# Ch5and6.net
KiCad netlist of a schematic drawn in Altium Designer
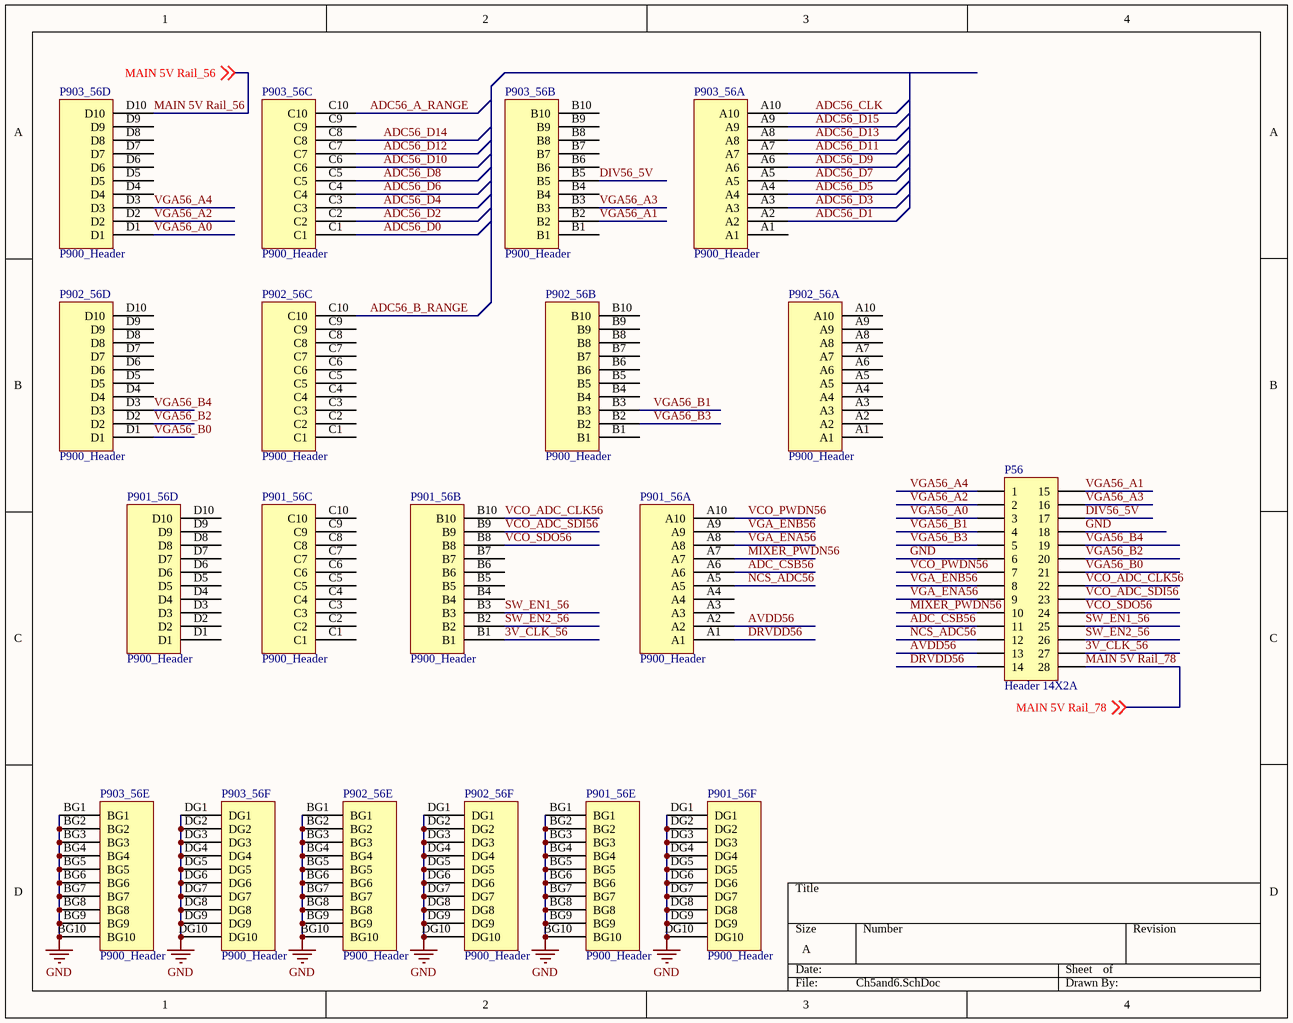
[diagram p0: Ch5and6.SchDoc]

(export (version "E")
  (design (tool "Eeschema 10.0.6"))
  (components
    (comp (ref "P56")
      (value "Header 14X2A")
      (footprint "HDR2X14_CEN")
      (description "Header, 14-Pin, Dual row")
      (fields (field (name "PUBLISHER") "Altium Limited"))
      (libsource (lib "Miscellaneous Connectors") (part "Header 14X2A"))
    )
    (comp (ref "P901_56")
      (value "P900_Header")
      (footprint "P900_header")
      (libsource (lib "") (part "P900_Header_1"))
    )
    (comp (ref "P902_56")
      (value "P900_Header")
      (footprint "P900_header")
      (libsource (lib "") (part "P900_Header_1"))
    )
    (comp (ref "P903_56")
      (value "P900_Header")
      (footprint "P900_header")
      (libsource (lib "MQP_lib") (part "P900_Header"))
    )
  )
  (nets
    (net (code "1") (name "/3V_CLK_56") (class "Default")
      (node (ref "P56") (pin "27") (pinfunction "27_27") (pintype "passive"))
      (node (ref "P901_56") (pin "B1") (pinfunction "B1_B1") (pintype "passive"))
    )
    (net (code "2") (name "/ADC56_A_RANGE") (class "Default")
      (node (ref "P903_56") (pin "C10") (pinfunction "C10_C10") (pintype "passive"))
    )
    (net (code "3") (name "/ADC56_B_RANGE") (class "Default")
      (node (ref "P902_56") (pin "C10") (pinfunction "C10_C10") (pintype "passive"))
    )
    (net (code "4") (name "/ADC56_CLK") (class "Default")
      (node (ref "P903_56") (pin "A10") (pinfunction "A10_A10") (pintype "passive"))
    )
    (net (code "5") (name "/ADC56_D0") (class "Default")
      (node (ref "P903_56") (pin "C1") (pinfunction "C1_C1") (pintype "passive"))
    )
    (net (code "6") (name "/ADC56_D1") (class "Default")
      (node (ref "P903_56") (pin "A2") (pinfunction "A2_A2") (pintype "passive"))
    )
    (net (code "7") (name "/ADC56_D2") (class "Default")
      (node (ref "P903_56") (pin "C2") (pinfunction "C2_C2") (pintype "passive"))
    )
    (net (code "8") (name "/ADC56_D3") (class "Default")
      (node (ref "P903_56") (pin "A3") (pinfunction "A3_A3") (pintype "passive"))
    )
    (net (code "9") (name "/ADC56_D4") (class "Default")
      (node (ref "P903_56") (pin "C3") (pinfunction "C3_C3") (pintype "passive"))
    )
    (net (code "10") (name "/ADC56_D5") (class "Default")
      (node (ref "P903_56") (pin "A4") (pinfunction "A4_A4") (pintype "passive"))
    )
    (net (code "11") (name "/ADC56_D6") (class "Default")
      (node (ref "P903_56") (pin "C4") (pinfunction "C4_C4") (pintype "passive"))
    )
    (net (code "12") (name "/ADC56_D7") (class "Default")
      (node (ref "P903_56") (pin "A5") (pinfunction "A5_A5") (pintype "passive"))
    )
    (net (code "13") (name "/ADC56_D8") (class "Default")
      (node (ref "P903_56") (pin "C5") (pinfunction "C5_C5") (pintype "passive"))
    )
    (net (code "14") (name "/ADC56_D9") (class "Default")
      (node (ref "P903_56") (pin "A6") (pinfunction "A6_A6") (pintype "passive"))
    )
    (net (code "15") (name "/ADC56_D10") (class "Default")
      (node (ref "P903_56") (pin "C6") (pinfunction "C6_C6") (pintype "passive"))
    )
    (net (code "16") (name "/ADC56_D11") (class "Default")
      (node (ref "P903_56") (pin "A7") (pinfunction "A7_A7") (pintype "passive"))
    )
    (net (code "17") (name "/ADC56_D12") (class "Default")
      (node (ref "P903_56") (pin "C7") (pinfunction "C7_C7") (pintype "passive"))
    )
    (net (code "18") (name "/ADC56_D13") (class "Default")
      (node (ref "P903_56") (pin "A8") (pinfunction "A8_A8") (pintype "passive"))
    )
    (net (code "19") (name "/ADC56_D14") (class "Default")
      (node (ref "P903_56") (pin "C8") (pinfunction "C8_C8") (pintype "passive"))
    )
    (net (code "20") (name "/ADC56_D15") (class "Default")
      (node (ref "P903_56") (pin "A9") (pinfunction "A9_A9") (pintype "passive"))
    )
    (net (code "21") (name "/ADC_CSB56") (class "Default")
      (node (ref "P56") (pin "11") (pinfunction "11_11") (pintype "passive"))
      (node (ref "P901_56") (pin "A6") (pinfunction "A6_A6") (pintype "passive"))
    )
    (net (code "22") (name "/AVDD56") (class "Default")
      (node (ref "P56") (pin "13") (pinfunction "13_13") (pintype "passive"))
      (node (ref "P901_56") (pin "A2") (pinfunction "A2_A2") (pintype "passive"))
    )
    (net (code "23") (name "/DIV56_5V") (class "Default")
      (node (ref "P56") (pin "17") (pinfunction "17_17") (pintype "passive"))
      (node (ref "P903_56") (pin "B5") (pinfunction "B5_B5") (pintype "passive"))
    )
    (net (code "24") (name "/DRVDD56") (class "Default")
      (node (ref "P56") (pin "14") (pinfunction "14_14") (pintype "passive"))
      (node (ref "P901_56") (pin "A1") (pinfunction "A1_A1") (pintype "passive"))
    )
    (net (code "25") (name "/MIXER_PWDN56") (class "Default")
      (node (ref "P56") (pin "10") (pinfunction "10_10") (pintype "passive"))
      (node (ref "P901_56") (pin "A7") (pinfunction "A7_A7") (pintype "passive"))
    )
    (net (code "26") (name "/NCS_ADC56") (class "Default")
      (node (ref "P56") (pin "12") (pinfunction "12_12") (pintype "passive"))
      (node (ref "P901_56") (pin "A5") (pinfunction "A5_A5") (pintype "passive"))
    )
    (net (code "27") (name "/SW_EN1_56") (class "Default")
      (node (ref "P56") (pin "25") (pinfunction "25_25") (pintype "passive"))
      (node (ref "P901_56") (pin "B3") (pinfunction "B3_B3") (pintype "passive"))
    )
    (net (code "28") (name "/SW_EN2_56") (class "Default")
      (node (ref "P56") (pin "26") (pinfunction "26_26") (pintype "passive"))
      (node (ref "P901_56") (pin "B2") (pinfunction "B2_B2") (pintype "passive"))
    )
    (net (code "29") (name "/VCO_ADC_CLK56") (class "Default")
      (node (ref "P56") (pin "22") (pinfunction "22_22") (pintype "passive"))
      (node (ref "P901_56") (pin "B10") (pinfunction "B10_B10") (pintype "passive"))
    )
    (net (code "30") (name "/VCO_ADC_SDI56") (class "Default")
      (node (ref "P56") (pin "23") (pinfunction "23_23") (pintype "passive"))
      (node (ref "P901_56") (pin "B9") (pinfunction "B9_B9") (pintype "passive"))
    )
    (net (code "31") (name "/VCO_PWDN56") (class "Default")
      (node (ref "P56") (pin "7") (pinfunction "7_7") (pintype "passive"))
      (node (ref "P901_56") (pin "A10") (pinfunction "A10_A10") (pintype "passive"))
    )
    (net (code "32") (name "/VCO_SDO56") (class "Default")
      (node (ref "P56") (pin "24") (pinfunction "24_24") (pintype "passive"))
      (node (ref "P901_56") (pin "B8") (pinfunction "B8_B8") (pintype "passive"))
    )
    (net (code "33") (name "/VGA56_A0") (class "Default")
      (node (ref "P56") (pin "3") (pinfunction "3_3") (pintype "passive"))
      (node (ref "P903_56") (pin "D1") (pinfunction "D1_D1") (pintype "passive"))
    )
    (net (code "34") (name "/VGA56_A1") (class "Default")
      (node (ref "P56") (pin "15") (pinfunction "15_15") (pintype "passive"))
      (node (ref "P903_56") (pin "B2") (pinfunction "B2_B2") (pintype "passive"))
    )
    (net (code "35") (name "/VGA56_A2") (class "Default")
      (node (ref "P56") (pin "2") (pinfunction "2_2") (pintype "passive"))
      (node (ref "P903_56") (pin "D2") (pinfunction "D2_D2") (pintype "passive"))
    )
    (net (code "36") (name "/VGA56_A3") (class "Default")
      (node (ref "P56") (pin "16") (pinfunction "16_16") (pintype "passive"))
      (node (ref "P903_56") (pin "B3") (pinfunction "B3_B3") (pintype "passive"))
    )
    (net (code "37") (name "/VGA56_A4") (class "Default")
      (node (ref "P56") (pin "1") (pinfunction "1_1") (pintype "passive"))
      (node (ref "P903_56") (pin "D3") (pinfunction "D3_D3") (pintype "passive"))
    )
    (net (code "38") (name "/VGA56_B0") (class "Default")
      (node (ref "P56") (pin "21") (pinfunction "21_21") (pintype "passive"))
      (node (ref "P902_56") (pin "D1") (pinfunction "D1_D1") (pintype "passive"))
    )
    (net (code "39") (name "/VGA56_B1") (class "Default")
      (node (ref "P56") (pin "4") (pinfunction "4_4") (pintype "passive"))
      (node (ref "P902_56") (pin "B3") (pinfunction "B3_B3") (pintype "passive"))
    )
    (net (code "40") (name "/VGA56_B2") (class "Default")
      (node (ref "P56") (pin "20") (pinfunction "20_20") (pintype "passive"))
      (node (ref "P902_56") (pin "D2") (pinfunction "D2_D2") (pintype "passive"))
    )
    (net (code "41") (name "/VGA56_B3") (class "Default")
      (node (ref "P56") (pin "5") (pinfunction "5_5") (pintype "passive"))
      (node (ref "P902_56") (pin "B2") (pinfunction "B2_B2") (pintype "passive"))
    )
    (net (code "42") (name "/VGA56_B4") (class "Default")
      (node (ref "P56") (pin "19") (pinfunction "19_19") (pintype "passive"))
      (node (ref "P902_56") (pin "D3") (pinfunction "D3_D3") (pintype "passive"))
    )
    (net (code "43") (name "/VGA_ENA56") (class "Default")
      (node (ref "P56") (pin "9") (pinfunction "9_9") (pintype "passive"))
      (node (ref "P901_56") (pin "A8") (pinfunction "A8_A8") (pintype "passive"))
    )
    (net (code "44") (name "/VGA_ENB56") (class "Default")
      (node (ref "P56") (pin "8") (pinfunction "8_8") (pintype "passive"))
      (node (ref "P901_56") (pin "A9") (pinfunction "A9_A9") (pintype "passive"))
    )
    (net (code "45") (name "GND") (class "Default")
      (node (ref "P56") (pin "18") (pinfunction "18_18") (pintype "passive"))
      (node (ref "P56") (pin "6") (pinfunction "6_6") (pintype "passive"))
      (node (ref "P901_56") (pin "BG1") (pinfunction "BG1_BG1") (pintype "passive"))
      (node (ref "P901_56") (pin "BG10") (pinfunction "BG10_BG10") (pintype "passive"))
      (node (ref "P901_56") (pin "BG2") (pinfunction "BG2_BG2") (pintype "passive"))
      (node (ref "P901_56") (pin "BG3") (pinfunction "BG3_BG3") (pintype "passive"))
      (node (ref "P901_56") (pin "BG4") (pinfunction "BG4_BG4") (pintype "passive"))
      (node (ref "P901_56") (pin "BG5") (pinfunction "BG5_BG5") (pintype "passive"))
      (node (ref "P901_56") (pin "BG6") (pinfunction "BG6_BG6") (pintype "passive"))
      (node (ref "P901_56") (pin "BG7") (pinfunction "BG7_BG7") (pintype "passive"))
      (node (ref "P901_56") (pin "BG8") (pinfunction "BG8_BG8") (pintype "passive"))
      (node (ref "P901_56") (pin "BG9") (pinfunction "BG9_BG9") (pintype "passive"))
      (node (ref "P901_56") (pin "DG1") (pinfunction "DG1_DG1") (pintype "passive"))
      (node (ref "P901_56") (pin "DG10") (pinfunction "DG10_DG10") (pintype "passive"))
      (node (ref "P901_56") (pin "DG2") (pinfunction "DG2_DG2") (pintype "passive"))
      (node (ref "P901_56") (pin "DG3") (pinfunction "DG3_DG3") (pintype "passive"))
      (node (ref "P901_56") (pin "DG4") (pinfunction "DG4_DG4") (pintype "passive"))
      (node (ref "P901_56") (pin "DG5") (pinfunction "DG5_DG5") (pintype "passive"))
      (node (ref "P901_56") (pin "DG6") (pinfunction "DG6_DG6") (pintype "passive"))
      (node (ref "P901_56") (pin "DG7") (pinfunction "DG7_DG7") (pintype "passive"))
      (node (ref "P901_56") (pin "DG8") (pinfunction "DG8_DG8") (pintype "passive"))
      (node (ref "P901_56") (pin "DG9") (pinfunction "DG9_DG9") (pintype "passive"))
      (node (ref "P902_56") (pin "BG1") (pinfunction "BG1_BG1") (pintype "passive"))
      (node (ref "P902_56") (pin "BG10") (pinfunction "BG10_BG10") (pintype "passive"))
      (node (ref "P902_56") (pin "BG2") (pinfunction "BG2_BG2") (pintype "passive"))
      (node (ref "P902_56") (pin "BG3") (pinfunction "BG3_BG3") (pintype "passive"))
      (node (ref "P902_56") (pin "BG4") (pinfunction "BG4_BG4") (pintype "passive"))
      (node (ref "P902_56") (pin "BG5") (pinfunction "BG5_BG5") (pintype "passive"))
      (node (ref "P902_56") (pin "BG6") (pinfunction "BG6_BG6") (pintype "passive"))
      (node (ref "P902_56") (pin "BG7") (pinfunction "BG7_BG7") (pintype "passive"))
      (node (ref "P902_56") (pin "BG8") (pinfunction "BG8_BG8") (pintype "passive"))
      (node (ref "P902_56") (pin "BG9") (pinfunction "BG9_BG9") (pintype "passive"))
      (node (ref "P902_56") (pin "DG1") (pinfunction "DG1_DG1") (pintype "passive"))
      (node (ref "P902_56") (pin "DG10") (pinfunction "DG10_DG10") (pintype "passive"))
      (node (ref "P902_56") (pin "DG2") (pinfunction "DG2_DG2") (pintype "passive"))
      (node (ref "P902_56") (pin "DG3") (pinfunction "DG3_DG3") (pintype "passive"))
      (node (ref "P902_56") (pin "DG4") (pinfunction "DG4_DG4") (pintype "passive"))
      (node (ref "P902_56") (pin "DG5") (pinfunction "DG5_DG5") (pintype "passive"))
      (node (ref "P902_56") (pin "DG6") (pinfunction "DG6_DG6") (pintype "passive"))
      (node (ref "P902_56") (pin "DG7") (pinfunction "DG7_DG7") (pintype "passive"))
      (node (ref "P902_56") (pin "DG8") (pinfunction "DG8_DG8") (pintype "passive"))
      (node (ref "P902_56") (pin "DG9") (pinfunction "DG9_DG9") (pintype "passive"))
      (node (ref "P903_56") (pin "BG1") (pinfunction "BG1_BG1") (pintype "passive"))
      (node (ref "P903_56") (pin "BG10") (pinfunction "BG10_BG10") (pintype "passive"))
      (node (ref "P903_56") (pin "BG2") (pinfunction "BG2_BG2") (pintype "passive"))
      (node (ref "P903_56") (pin "BG3") (pinfunction "BG3_BG3") (pintype "passive"))
      (node (ref "P903_56") (pin "BG4") (pinfunction "BG4_BG4") (pintype "passive"))
      (node (ref "P903_56") (pin "BG5") (pinfunction "BG5_BG5") (pintype "passive"))
      (node (ref "P903_56") (pin "BG6") (pinfunction "BG6_BG6") (pintype "passive"))
      (node (ref "P903_56") (pin "BG7") (pinfunction "BG7_BG7") (pintype "passive"))
      (node (ref "P903_56") (pin "BG8") (pinfunction "BG8_BG8") (pintype "passive"))
      (node (ref "P903_56") (pin "BG9") (pinfunction "BG9_BG9") (pintype "passive"))
      (node (ref "P903_56") (pin "DG1") (pinfunction "DG1_DG1") (pintype "passive"))
      (node (ref "P903_56") (pin "DG10") (pinfunction "DG10_DG10") (pintype "passive"))
      (node (ref "P903_56") (pin "DG2") (pinfunction "DG2_DG2") (pintype "passive"))
      (node (ref "P903_56") (pin "DG3") (pinfunction "DG3_DG3") (pintype "passive"))
      (node (ref "P903_56") (pin "DG4") (pinfunction "DG4_DG4") (pintype "passive"))
      (node (ref "P903_56") (pin "DG5") (pinfunction "DG5_DG5") (pintype "passive"))
      (node (ref "P903_56") (pin "DG6") (pinfunction "DG6_DG6") (pintype "passive"))
      (node (ref "P903_56") (pin "DG7") (pinfunction "DG7_DG7") (pintype "passive"))
      (node (ref "P903_56") (pin "DG8") (pinfunction "DG8_DG8") (pintype "passive"))
      (node (ref "P903_56") (pin "DG9") (pinfunction "DG9_DG9") (pintype "passive"))
    )
    (net (code "46") (name "MAIN 5V Rail_56") (class "Default")
      (node (ref "P903_56") (pin "D10") (pinfunction "D10_D10") (pintype "passive"))
    )
    (net (code "47") (name "MAIN 5V Rail_78") (class "Default")
      (node (ref "P56") (pin "28") (pinfunction "28_28") (pintype "passive"))
    )
    (net (code "48") (name "unconnected-(P901_56-PadA3)") (class "Default")
      (node (ref "P901_56") (pin "A3") (pinfunction "A3_A3") (pintype "passive"))
    )
    (net (code "49") (name "unconnected-(P901_56-PadA4)") (class "Default")
      (node (ref "P901_56") (pin "A4") (pinfunction "A4_A4") (pintype "passive"))
    )
    (net (code "50") (name "unconnected-(P901_56-PadB4)") (class "Default")
      (node (ref "P901_56") (pin "B4") (pinfunction "B4_B4") (pintype "passive"))
    )
    (net (code "51") (name "unconnected-(P901_56-PadB5)") (class "Default")
      (node (ref "P901_56") (pin "B5") (pinfunction "B5_B5") (pintype "passive"))
    )
    (net (code "52") (name "unconnected-(P901_56-PadB6)") (class "Default")
      (node (ref "P901_56") (pin "B6") (pinfunction "B6_B6") (pintype "passive"))
    )
    (net (code "53") (name "unconnected-(P901_56-PadB7)") (class "Default")
      (node (ref "P901_56") (pin "B7") (pinfunction "B7_B7") (pintype "passive"))
    )
    (net (code "54") (name "unconnected-(P901_56-PadC1)") (class "Default")
      (node (ref "P901_56") (pin "C1") (pinfunction "C1_C1") (pintype "passive"))
    )
    (net (code "55") (name "unconnected-(P901_56-PadC2)") (class "Default")
      (node (ref "P901_56") (pin "C2") (pinfunction "C2_C2") (pintype "passive"))
    )
    (net (code "56") (name "unconnected-(P901_56-PadC3)") (class "Default")
      (node (ref "P901_56") (pin "C3") (pinfunction "C3_C3") (pintype "passive"))
    )
    (net (code "57") (name "unconnected-(P901_56-PadC4)") (class "Default")
      (node (ref "P901_56") (pin "C4") (pinfunction "C4_C4") (pintype "passive"))
    )
    (net (code "58") (name "unconnected-(P901_56-PadC5)") (class "Default")
      (node (ref "P901_56") (pin "C5") (pinfunction "C5_C5") (pintype "passive"))
    )
    (net (code "59") (name "unconnected-(P901_56-PadC6)") (class "Default")
      (node (ref "P901_56") (pin "C6") (pinfunction "C6_C6") (pintype "passive"))
    )
    (net (code "60") (name "unconnected-(P901_56-PadC7)") (class "Default")
      (node (ref "P901_56") (pin "C7") (pinfunction "C7_C7") (pintype "passive"))
    )
    (net (code "61") (name "unconnected-(P901_56-PadC8)") (class "Default")
      (node (ref "P901_56") (pin "C8") (pinfunction "C8_C8") (pintype "passive"))
    )
    (net (code "62") (name "unconnected-(P901_56-PadC9)") (class "Default")
      (node (ref "P901_56") (pin "C9") (pinfunction "C9_C9") (pintype "passive"))
    )
    (net (code "63") (name "unconnected-(P901_56-PadC10)") (class "Default")
      (node (ref "P901_56") (pin "C10") (pinfunction "C10_C10") (pintype "passive"))
    )
    (net (code "64") (name "unconnected-(P901_56-PadD1)") (class "Default")
      (node (ref "P901_56") (pin "D1") (pinfunction "D1_D1") (pintype "passive"))
    )
    (net (code "65") (name "unconnected-(P901_56-PadD2)") (class "Default")
      (node (ref "P901_56") (pin "D2") (pinfunction "D2_D2") (pintype "passive"))
    )
    (net (code "66") (name "unconnected-(P901_56-PadD3)") (class "Default")
      (node (ref "P901_56") (pin "D3") (pinfunction "D3_D3") (pintype "passive"))
    )
    (net (code "67") (name "unconnected-(P901_56-PadD4)") (class "Default")
      (node (ref "P901_56") (pin "D4") (pinfunction "D4_D4") (pintype "passive"))
    )
    (net (code "68") (name "unconnected-(P901_56-PadD5)") (class "Default")
      (node (ref "P901_56") (pin "D5") (pinfunction "D5_D5") (pintype "passive"))
    )
    (net (code "69") (name "unconnected-(P901_56-PadD6)") (class "Default")
      (node (ref "P901_56") (pin "D6") (pinfunction "D6_D6") (pintype "passive"))
    )
    (net (code "70") (name "unconnected-(P901_56-PadD7)") (class "Default")
      (node (ref "P901_56") (pin "D7") (pinfunction "D7_D7") (pintype "passive"))
    )
    (net (code "71") (name "unconnected-(P901_56-PadD8)") (class "Default")
      (node (ref "P901_56") (pin "D8") (pinfunction "D8_D8") (pintype "passive"))
    )
    (net (code "72") (name "unconnected-(P901_56-PadD9)") (class "Default")
      (node (ref "P901_56") (pin "D9") (pinfunction "D9_D9") (pintype "passive"))
    )
    (net (code "73") (name "unconnected-(P901_56-PadD10)") (class "Default")
      (node (ref "P901_56") (pin "D10") (pinfunction "D10_D10") (pintype "passive"))
    )
    (net (code "74") (name "unconnected-(P902_56-PadA1)") (class "Default")
      (node (ref "P902_56") (pin "A1") (pinfunction "A1_A1") (pintype "passive"))
    )
    (net (code "75") (name "unconnected-(P902_56-PadA2)") (class "Default")
      (node (ref "P902_56") (pin "A2") (pinfunction "A2_A2") (pintype "passive"))
    )
    (net (code "76") (name "unconnected-(P902_56-PadA3)") (class "Default")
      (node (ref "P902_56") (pin "A3") (pinfunction "A3_A3") (pintype "passive"))
    )
    (net (code "77") (name "unconnected-(P902_56-PadA4)") (class "Default")
      (node (ref "P902_56") (pin "A4") (pinfunction "A4_A4") (pintype "passive"))
    )
    (net (code "78") (name "unconnected-(P902_56-PadA5)") (class "Default")
      (node (ref "P902_56") (pin "A5") (pinfunction "A5_A5") (pintype "passive"))
    )
    (net (code "79") (name "unconnected-(P902_56-PadA6)") (class "Default")
      (node (ref "P902_56") (pin "A6") (pinfunction "A6_A6") (pintype "passive"))
    )
    (net (code "80") (name "unconnected-(P902_56-PadA7)") (class "Default")
      (node (ref "P902_56") (pin "A7") (pinfunction "A7_A7") (pintype "passive"))
    )
    (net (code "81") (name "unconnected-(P902_56-PadA8)") (class "Default")
      (node (ref "P902_56") (pin "A8") (pinfunction "A8_A8") (pintype "passive"))
    )
    (net (code "82") (name "unconnected-(P902_56-PadA9)") (class "Default")
      (node (ref "P902_56") (pin "A9") (pinfunction "A9_A9") (pintype "passive"))
    )
    (net (code "83") (name "unconnected-(P902_56-PadA10)") (class "Default")
      (node (ref "P902_56") (pin "A10") (pinfunction "A10_A10") (pintype "passive"))
    )
    (net (code "84") (name "unconnected-(P902_56-PadB1)") (class "Default")
      (node (ref "P902_56") (pin "B1") (pinfunction "B1_B1") (pintype "passive"))
    )
    (net (code "85") (name "unconnected-(P902_56-PadB4)") (class "Default")
      (node (ref "P902_56") (pin "B4") (pinfunction "B4_B4") (pintype "passive"))
    )
    (net (code "86") (name "unconnected-(P902_56-PadB5)") (class "Default")
      (node (ref "P902_56") (pin "B5") (pinfunction "B5_B5") (pintype "passive"))
    )
    (net (code "87") (name "unconnected-(P902_56-PadB6)") (class "Default")
      (node (ref "P902_56") (pin "B6") (pinfunction "B6_B6") (pintype "passive"))
    )
    (net (code "88") (name "unconnected-(P902_56-PadB7)") (class "Default")
      (node (ref "P902_56") (pin "B7") (pinfunction "B7_B7") (pintype "passive"))
    )
    (net (code "89") (name "unconnected-(P902_56-PadB8)") (class "Default")
      (node (ref "P902_56") (pin "B8") (pinfunction "B8_B8") (pintype "passive"))
    )
    (net (code "90") (name "unconnected-(P902_56-PadB9)") (class "Default")
      (node (ref "P902_56") (pin "B9") (pinfunction "B9_B9") (pintype "passive"))
    )
    (net (code "91") (name "unconnected-(P902_56-PadB10)") (class "Default")
      (node (ref "P902_56") (pin "B10") (pinfunction "B10_B10") (pintype "passive"))
    )
    (net (code "92") (name "unconnected-(P902_56-PadC1)") (class "Default")
      (node (ref "P902_56") (pin "C1") (pinfunction "C1_C1") (pintype "passive"))
    )
    (net (code "93") (name "unconnected-(P902_56-PadC2)") (class "Default")
      (node (ref "P902_56") (pin "C2") (pinfunction "C2_C2") (pintype "passive"))
    )
    (net (code "94") (name "unconnected-(P902_56-PadC3)") (class "Default")
      (node (ref "P902_56") (pin "C3") (pinfunction "C3_C3") (pintype "passive"))
    )
    (net (code "95") (name "unconnected-(P902_56-PadC4)") (class "Default")
      (node (ref "P902_56") (pin "C4") (pinfunction "C4_C4") (pintype "passive"))
    )
    (net (code "96") (name "unconnected-(P902_56-PadC5)") (class "Default")
      (node (ref "P902_56") (pin "C5") (pinfunction "C5_C5") (pintype "passive"))
    )
    (net (code "97") (name "unconnected-(P902_56-PadC6)") (class "Default")
      (node (ref "P902_56") (pin "C6") (pinfunction "C6_C6") (pintype "passive"))
    )
    (net (code "98") (name "unconnected-(P902_56-PadC7)") (class "Default")
      (node (ref "P902_56") (pin "C7") (pinfunction "C7_C7") (pintype "passive"))
    )
    (net (code "99") (name "unconnected-(P902_56-PadC8)") (class "Default")
      (node (ref "P902_56") (pin "C8") (pinfunction "C8_C8") (pintype "passive"))
    )
    (net (code "100") (name "unconnected-(P902_56-PadC9)") (class "Default")
      (node (ref "P902_56") (pin "C9") (pinfunction "C9_C9") (pintype "passive"))
    )
    (net (code "101") (name "unconnected-(P902_56-PadD4)") (class "Default")
      (node (ref "P902_56") (pin "D4") (pinfunction "D4_D4") (pintype "passive"))
    )
    (net (code "102") (name "unconnected-(P902_56-PadD5)") (class "Default")
      (node (ref "P902_56") (pin "D5") (pinfunction "D5_D5") (pintype "passive"))
    )
    (net (code "103") (name "unconnected-(P902_56-PadD6)") (class "Default")
      (node (ref "P902_56") (pin "D6") (pinfunction "D6_D6") (pintype "passive"))
    )
    (net (code "104") (name "unconnected-(P902_56-PadD7)") (class "Default")
      (node (ref "P902_56") (pin "D7") (pinfunction "D7_D7") (pintype "passive"))
    )
    (net (code "105") (name "unconnected-(P902_56-PadD8)") (class "Default")
      (node (ref "P902_56") (pin "D8") (pinfunction "D8_D8") (pintype "passive"))
    )
    (net (code "106") (name "unconnected-(P902_56-PadD9)") (class "Default")
      (node (ref "P902_56") (pin "D9") (pinfunction "D9_D9") (pintype "passive"))
    )
    (net (code "107") (name "unconnected-(P902_56-PadD10)") (class "Default")
      (node (ref "P902_56") (pin "D10") (pinfunction "D10_D10") (pintype "passive"))
    )
    (net (code "108") (name "unconnected-(P903_56-PadA1)") (class "Default")
      (node (ref "P903_56") (pin "A1") (pinfunction "A1_A1") (pintype "passive"))
    )
    (net (code "109") (name "unconnected-(P903_56-PadB1)") (class "Default")
      (node (ref "P903_56") (pin "B1") (pinfunction "B1_B1") (pintype "passive"))
    )
    (net (code "110") (name "unconnected-(P903_56-PadB4)") (class "Default")
      (node (ref "P903_56") (pin "B4") (pinfunction "B4_B4") (pintype "passive"))
    )
    (net (code "111") (name "unconnected-(P903_56-PadB6)") (class "Default")
      (node (ref "P903_56") (pin "B6") (pinfunction "B6_B6") (pintype "passive"))
    )
    (net (code "112") (name "unconnected-(P903_56-PadB7)") (class "Default")
      (node (ref "P903_56") (pin "B7") (pinfunction "B7_B7") (pintype "passive"))
    )
    (net (code "113") (name "unconnected-(P903_56-PadB8)") (class "Default")
      (node (ref "P903_56") (pin "B8") (pinfunction "B8_B8") (pintype "passive"))
    )
    (net (code "114") (name "unconnected-(P903_56-PadB9)") (class "Default")
      (node (ref "P903_56") (pin "B9") (pinfunction "B9_B9") (pintype "passive"))
    )
    (net (code "115") (name "unconnected-(P903_56-PadB10)") (class "Default")
      (node (ref "P903_56") (pin "B10") (pinfunction "B10_B10") (pintype "passive"))
    )
    (net (code "116") (name "unconnected-(P903_56-PadC9)") (class "Default")
      (node (ref "P903_56") (pin "C9") (pinfunction "C9_C9") (pintype "passive"))
    )
    (net (code "117") (name "unconnected-(P903_56-PadD4)") (class "Default")
      (node (ref "P903_56") (pin "D4") (pinfunction "D4_D4") (pintype "passive"))
    )
    (net (code "118") (name "unconnected-(P903_56-PadD5)") (class "Default")
      (node (ref "P903_56") (pin "D5") (pinfunction "D5_D5") (pintype "passive"))
    )
    (net (code "119") (name "unconnected-(P903_56-PadD6)") (class "Default")
      (node (ref "P903_56") (pin "D6") (pinfunction "D6_D6") (pintype "passive"))
    )
    (net (code "120") (name "unconnected-(P903_56-PadD7)") (class "Default")
      (node (ref "P903_56") (pin "D7") (pinfunction "D7_D7") (pintype "passive"))
    )
    (net (code "121") (name "unconnected-(P903_56-PadD8)") (class "Default")
      (node (ref "P903_56") (pin "D8") (pinfunction "D8_D8") (pintype "passive"))
    )
    (net (code "122") (name "unconnected-(P903_56-PadD9)") (class "Default")
      (node (ref "P903_56") (pin "D9") (pinfunction "D9_D9") (pintype "passive"))
    )
  )
)
